# SenseGrain-v0_2.net
KiCad netlist of a schematic drawn in EAGLE
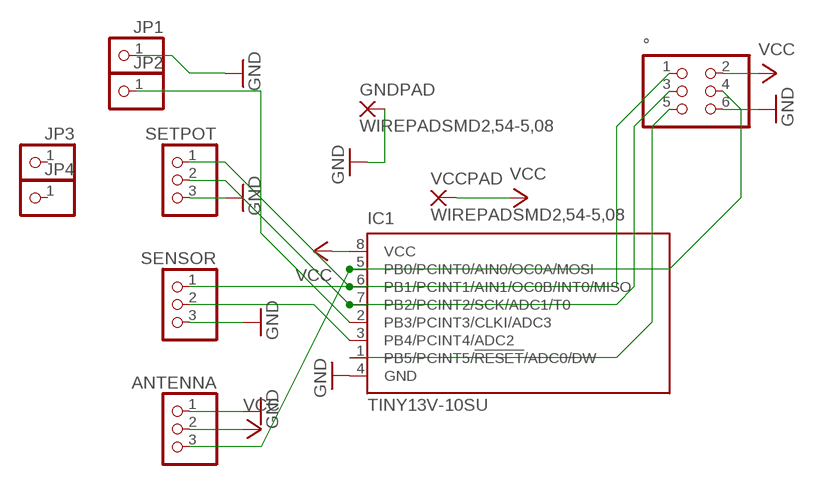
[diagram p0: schematic, sheet 1]

(export (version "E")
  (design (tool "Eeschema 10.0.6"))
  (components
    (comp (ref "ANTENNA")
      (value "PINHD-1X3CB")
      (footprint "eagle-import:1X03-CLEANBIG")
      (libsource (lib "eagle-import") (part "PINHD-1X3CB"))
    )
    (comp (ref "GNDPAD")
      (value "WIREPADSMD2,54-5,08")
      (footprint "eagle-import:SMD2,54-5,08")
      (libsource (lib "eagle-import") (part "WIREPADSMD2,54-5,08"))
    )
    (comp (ref "IC1")
      (value "TINY13V-10SU")
      (footprint "eagle-import:8S2")
      (fields (field (name "MPN") "ATTINY13V-10SU"))
      (libsource (lib "eagle-import") (part "TINY13SUV-10"))
    )
    (comp (ref "JP1")
      (value "PINHD-1X1")
      (footprint "eagle-import:1X01")
      (libsource (lib "eagle-import") (part "PINHD-1X1"))
    )
    (comp (ref "JP2")
      (value "PINHD-1X1")
      (footprint "eagle-import:1X01")
      (libsource (lib "eagle-import") (part "PINHD-1X1"))
    )
    (comp (ref "JP3")
      (value "PINHD-1X1")
      (footprint "eagle-import:1X01")
      (libsource (lib "eagle-import") (part "PINHD-1X1"))
    )
    (comp (ref "JP4")
      (value "PINHD-1X1")
      (footprint "eagle-import:1X01")
      (libsource (lib "eagle-import") (part "PINHD-1X1"))
    )
    (comp (ref "SENSOR")
      (value "PINHD-1X3CB")
      (footprint "eagle-import:1X03-CLEANBIG")
      (libsource (lib "eagle-import") (part "PINHD-1X3CB"))
    )
    (comp (ref "SETPOT")
      (value "PINHD-1X3CB")
      (footprint "eagle-import:1X03-CLEANBIG")
      (libsource (lib "eagle-import") (part "PINHD-1X3CB"))
    )
    (comp (ref "VCCPAD")
      (value "WIREPADSMD2,54-5,08")
      (footprint "eagle-import:SMD2,54-5,08")
      (libsource (lib "eagle-import") (part "WIREPADSMD2,54-5,08"))
    )
    (comp (ref "°")
      (value "PINHD-2X3")
      (footprint "eagle-import:2X03")
      (libsource (lib "eagle-import") (part "PINHD-2X3"))
    )
  )
  (nets
    (net (code "1") (name "GND") (class "Default")
      (node (ref "ANTENNA") (pin "1") (pinfunction "1_1") (pintype "passive"))
      (node (ref "GNDPAD") (pin "1") (pinfunction "P_1") (pintype "passive"))
      (node (ref "IC1") (pin "4") (pinfunction "GND_4") (pintype "power_in"))
      (node (ref "JP1") (pin "1") (pinfunction "1_1") (pintype "passive"))
      (node (ref "SENSOR") (pin "3") (pinfunction "3_3") (pintype "passive"))
      (node (ref "SETPOT") (pin "3") (pinfunction "3_3") (pintype "passive"))
      (node (ref "°") (pin "6") (pinfunction "6_6") (pintype "passive"))
    )
    (net (code "2") (name "Net-(IC1-PB0{slash}PCINT0{slash}AIN0{slash}OC0A{slash}MOSI)") (class "Default")
      (node (ref "ANTENNA") (pin "3") (pinfunction "3_3") (pintype "passive"))
      (node (ref "IC1") (pin "5") (pinfunction "PB0/PCINT0/AIN0/OC0A/MOSI_5") (pintype "bidirectional"))
      (node (ref "°") (pin "4") (pinfunction "4_4") (pintype "passive"))
    )
    (net (code "3") (name "Net-(IC1-PB1{slash}PCINT1{slash}AIN1{slash}OC0B{slash}INT0{slash}MISO)") (class "Default")
      (node (ref "IC1") (pin "6") (pinfunction "PB1/PCINT1/AIN1/OC0B/INT0/MISO_6") (pintype "bidirectional"))
      (node (ref "SENSOR") (pin "1") (pinfunction "1_1") (pintype "passive"))
      (node (ref "SETPOT") (pin "1") (pinfunction "1_1") (pintype "passive"))
      (node (ref "°") (pin "1") (pinfunction "1_1") (pintype "passive"))
    )
    (net (code "4") (name "Net-(IC1-PB2{slash}PCINT2{slash}SCK{slash}ADC1{slash}T0)") (class "Default")
      (node (ref "IC1") (pin "7") (pinfunction "PB2/PCINT2/SCK/ADC1/T0_7") (pintype "bidirectional"))
      (node (ref "SETPOT") (pin "2") (pinfunction "2_2") (pintype "passive"))
      (node (ref "°") (pin "3") (pinfunction "3_3") (pintype "passive"))
    )
    (net (code "5") (name "Net-(IC1-PB3{slash}PCINT3{slash}CLKI{slash}ADC3)") (class "Default")
      (node (ref "IC1") (pin "2") (pinfunction "PB3/PCINT3/CLKI/ADC3_2") (pintype "bidirectional"))
      (node (ref "JP2") (pin "1") (pinfunction "1_1") (pintype "passive"))
    )
    (net (code "6") (name "Net-(IC1-PB4{slash}PCINT4{slash}ADC2)") (class "Default")
      (node (ref "IC1") (pin "3") (pinfunction "PB4/PCINT4/ADC2_3") (pintype "bidirectional"))
      (node (ref "SENSOR") (pin "2") (pinfunction "2_2") (pintype "passive"))
    )
    (net (code "7") (name "Net-(IC1-PB5{slash}PCINT5{slash}~{RESET}{slash}ADC0{slash}DW)") (class "Default")
      (node (ref "IC1") (pin "1") (pinfunction "PB5/PCINT5/~{RESET}/ADC0/DW_1") (pintype "bidirectional"))
      (node (ref "°") (pin "5") (pinfunction "5_5") (pintype "passive"))
    )
    (net (code "8") (name "VCC") (class "Default")
      (node (ref "ANTENNA") (pin "2") (pinfunction "2_2") (pintype "passive"))
      (node (ref "IC1") (pin "8") (pinfunction "VCC_8") (pintype "power_in"))
      (node (ref "VCCPAD") (pin "1") (pinfunction "P_1") (pintype "passive"))
      (node (ref "°") (pin "2") (pinfunction "2_2") (pintype "passive"))
    )
    (net (code "9") (name "unconnected-(JP3-Pad1)") (class "Default")
      (node (ref "JP3") (pin "1") (pinfunction "1_1") (pintype "passive"))
    )
    (net (code "10") (name "unconnected-(JP4-Pad1)") (class "Default")
      (node (ref "JP4") (pin "1") (pinfunction "1_1") (pintype "passive"))
    )
  )
)
